# 0_8mm_Layers.net
KiCad netlist of a schematic drawn in EAGLE
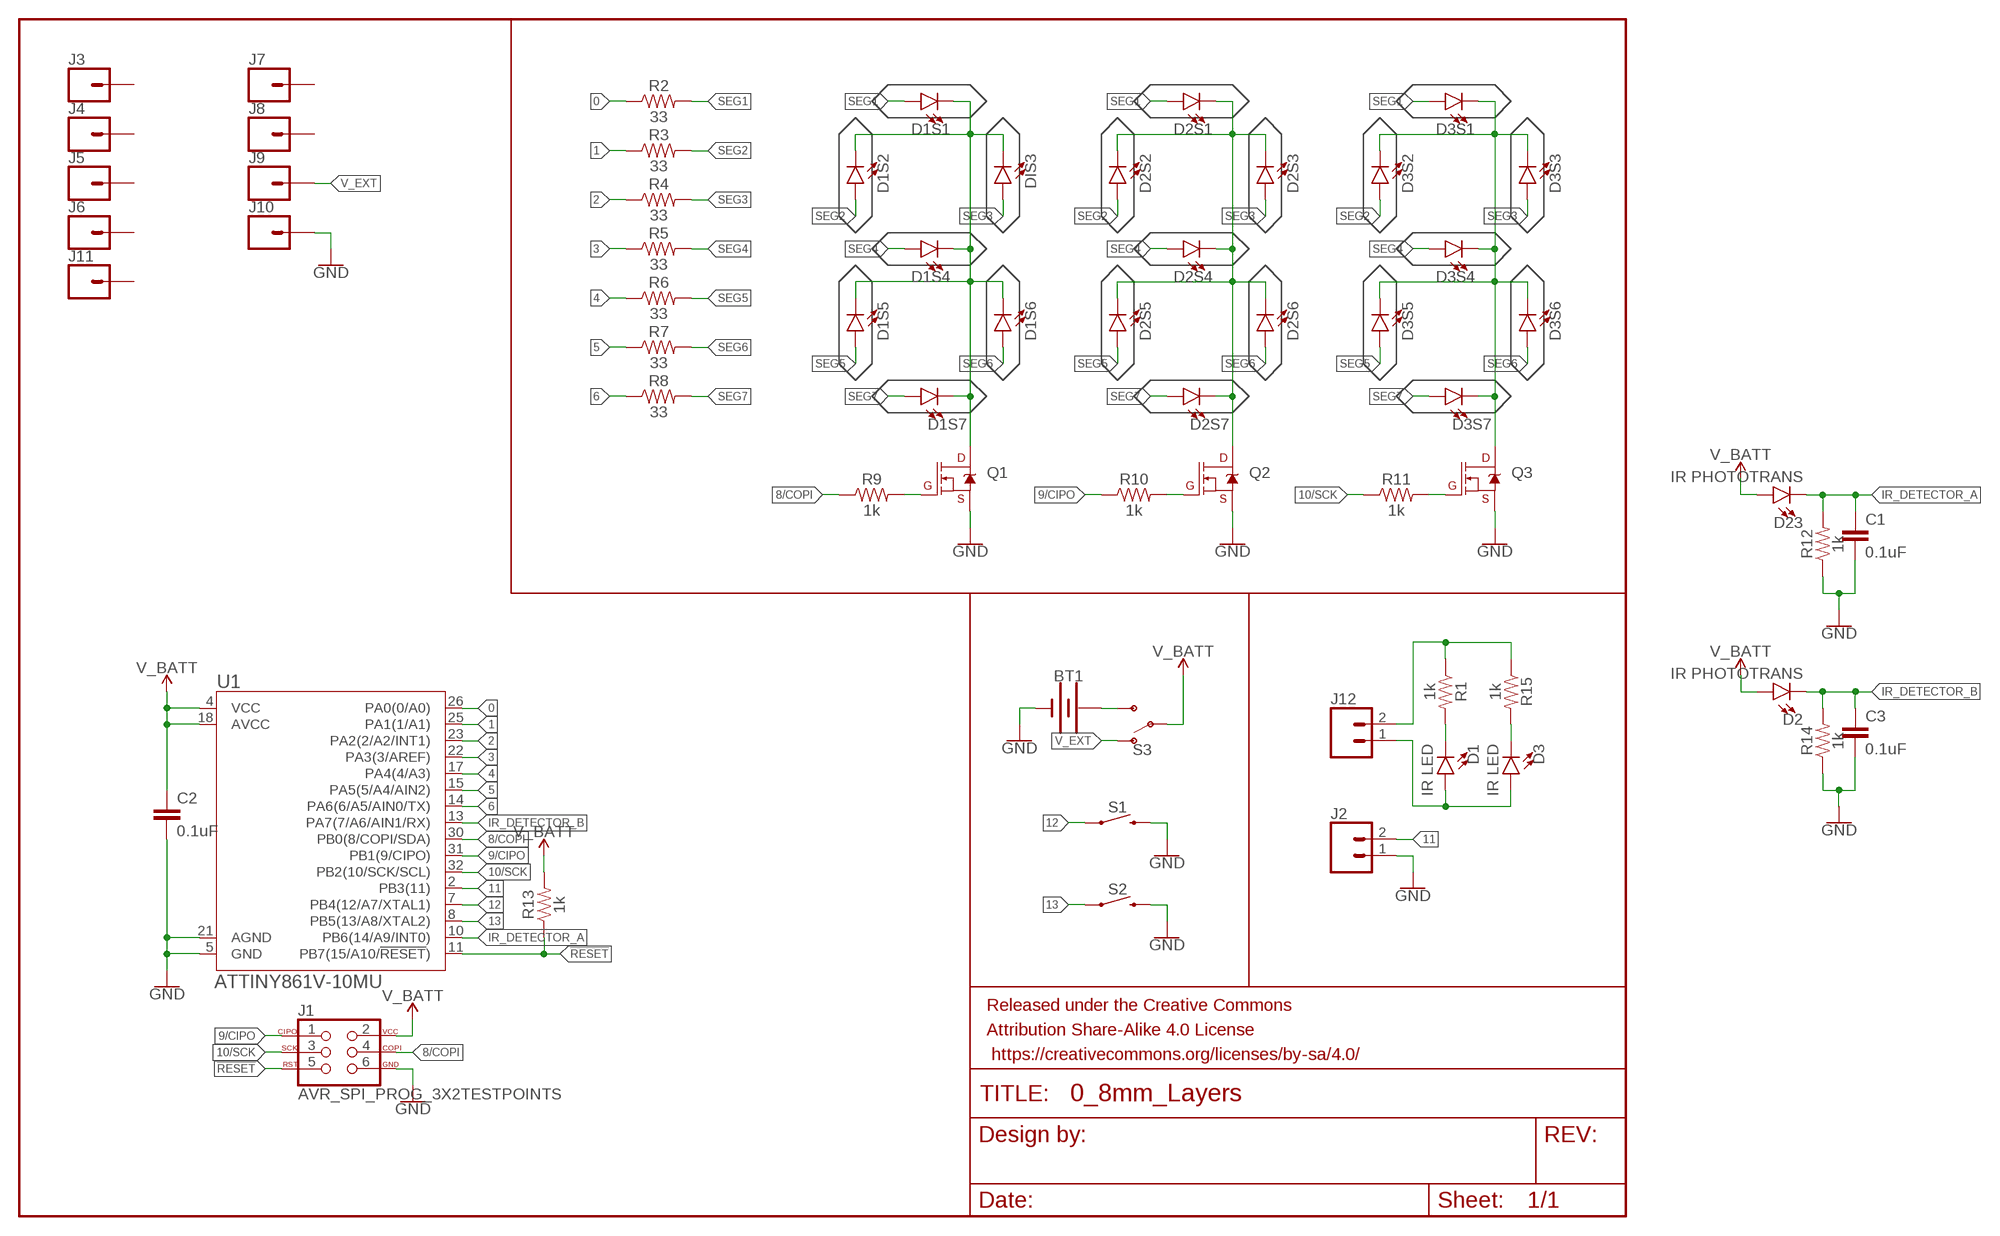
[diagram p0: schematic, sheet 1]

(export (version "E")
  (design (tool "Eeschema 10.0.6"))
  (components
    (comp (ref "BT1")
      (value "BATTERY-20MM_SMD_4LEGS_OVERPASTE_INNER")
      (footprint "eagle-import:BATTCON_20MM_4LEGS_OVERPASTE_INNER")
      (libsource (lib "eagle-import") (part "BATTERY-20MM_SMD_4LEGS_OVERPASTE_INNER"))
    )
    (comp (ref "C1")
      (value "0.1uF")
      (footprint "eagle-import:0603")
      (libsource (lib "eagle-import") (part "0.1UF-0603-25V-(+80/-20%)"))
    )
    (comp (ref "C2")
      (value "0.1uF")
      (footprint "eagle-import:0603")
      (libsource (lib "eagle-import") (part "0.1UF-0603-25V-(+80/-20%)"))
    )
    (comp (ref "C3")
      (value "0.1uF")
      (footprint "eagle-import:0603")
      (libsource (lib "eagle-import") (part "0.1UF-0603-25V-(+80/-20%)"))
    )
    (comp (ref "D1")
      (value "IR LED")
      (footprint "eagle-import:LED-0603")
      (libsource (lib "eagle-import") (part "LED-IR0603"))
    )
    (comp (ref "D1S1")
      (value "LED0603")
      (footprint "eagle-import:LED-0603")
      (libsource (lib "eagle-import") (part "LED0603"))
    )
    (comp (ref "D1S2")
      (value "LED0603")
      (footprint "eagle-import:LED-0603")
      (libsource (lib "eagle-import") (part "LED0603"))
    )
    (comp (ref "D1S4")
      (value "LED0603")
      (footprint "eagle-import:LED-0603")
      (libsource (lib "eagle-import") (part "LED0603"))
    )
    (comp (ref "D1S5")
      (value "LED0603")
      (footprint "eagle-import:LED-0603")
      (libsource (lib "eagle-import") (part "LED0603"))
    )
    (comp (ref "D1S6")
      (value "LED0603")
      (footprint "eagle-import:LED-0603")
      (libsource (lib "eagle-import") (part "LED0603"))
    )
    (comp (ref "D1S7")
      (value "LED0603")
      (footprint "eagle-import:LED-0603")
      (libsource (lib "eagle-import") (part "LED0603"))
    )
    (comp (ref "D2")
      (value "IR PHOTOTRANS")
      (footprint "eagle-import:LED-0603")
      (libsource (lib "eagle-import") (part "LED-IR0603"))
    )
    (comp (ref "D2S1")
      (value "LED0603")
      (footprint "eagle-import:LED-0603")
      (libsource (lib "eagle-import") (part "LED0603"))
    )
    (comp (ref "D2S2")
      (value "LED0603")
      (footprint "eagle-import:LED-0603")
      (libsource (lib "eagle-import") (part "LED0603"))
    )
    (comp (ref "D2S3")
      (value "LED0603")
      (footprint "eagle-import:LED-0603")
      (libsource (lib "eagle-import") (part "LED0603"))
    )
    (comp (ref "D2S4")
      (value "LED0603")
      (footprint "eagle-import:LED-0603")
      (libsource (lib "eagle-import") (part "LED0603"))
    )
    (comp (ref "D2S5")
      (value "LED0603")
      (footprint "eagle-import:LED-0603")
      (libsource (lib "eagle-import") (part "LED0603"))
    )
    (comp (ref "D2S6")
      (value "LED0603")
      (footprint "eagle-import:LED-0603")
      (libsource (lib "eagle-import") (part "LED0603"))
    )
    (comp (ref "D2S7")
      (value "LED0603")
      (footprint "eagle-import:LED-0603")
      (libsource (lib "eagle-import") (part "LED0603"))
    )
    (comp (ref "D3")
      (value "IR LED")
      (footprint "eagle-import:LED-0603")
      (libsource (lib "eagle-import") (part "LED-IR0603"))
    )
    (comp (ref "D3S1")
      (value "LED0603")
      (footprint "eagle-import:LED-0603")
      (libsource (lib "eagle-import") (part "LED0603"))
    )
    (comp (ref "D3S2")
      (value "LED0603")
      (footprint "eagle-import:LED-0603")
      (libsource (lib "eagle-import") (part "LED0603"))
    )
    (comp (ref "D3S3")
      (value "LED0603")
      (footprint "eagle-import:LED-0603")
      (libsource (lib "eagle-import") (part "LED0603"))
    )
    (comp (ref "D3S4")
      (value "LED0603")
      (footprint "eagle-import:LED-0603")
      (libsource (lib "eagle-import") (part "LED0603"))
    )
    (comp (ref "D3S5")
      (value "LED0603")
      (footprint "eagle-import:LED-0603")
      (libsource (lib "eagle-import") (part "LED0603"))
    )
    (comp (ref "D3S6")
      (value "LED0603")
      (footprint "eagle-import:LED-0603")
      (libsource (lib "eagle-import") (part "LED0603"))
    )
    (comp (ref "D3S7")
      (value "LED0603")
      (footprint "eagle-import:LED-0603")
      (libsource (lib "eagle-import") (part "LED0603"))
    )
    (comp (ref "D23")
      (value "IR PHOTOTRANS")
      (footprint "eagle-import:LED-0603")
      (libsource (lib "eagle-import") (part "LED-IR0603"))
    )
    (comp (ref "DIS3")
      (value "LED0603")
      (footprint "eagle-import:LED-0603")
      (libsource (lib "eagle-import") (part "LED0603"))
    )
    (comp (ref "FRAME1")
      (value "FRAME-LETTER")
      (footprint "eagle-import:CREATIVE_COMMONS")
      (libsource (lib "eagle-import") (part "FRAME-LETTER"))
    )
    (comp (ref "J1")
      (value "AVR_SPI_PROG_3X2TESTPOINTS")
      (footprint "eagle-import:2X3_TEST_POINTS")
      (libsource (lib "eagle-import") (part "AVR_SPI_PROG_3X2TESTPOINTS"))
    )
    (comp (ref "J2")
      (value "CONN_02")
      (footprint "eagle-import:1X02")
      (libsource (lib "eagle-import") (part "CONN_02"))
    )
    (comp (ref "J3")
      (value "CONN_01")
      (footprint "eagle-import:1X01")
      (libsource (lib "eagle-import") (part "CONN_01"))
    )
    (comp (ref "J4")
      (value "CONN_01")
      (footprint "eagle-import:1X01")
      (libsource (lib "eagle-import") (part "CONN_01"))
    )
    (comp (ref "J5")
      (value "CONN_01")
      (footprint "eagle-import:1X01")
      (libsource (lib "eagle-import") (part "CONN_01"))
    )
    (comp (ref "J6")
      (value "CONN_01")
      (footprint "eagle-import:1X01")
      (libsource (lib "eagle-import") (part "CONN_01"))
    )
    (comp (ref "J7")
      (value "CONN_01")
      (footprint "eagle-import:1X01")
      (libsource (lib "eagle-import") (part "CONN_01"))
    )
    (comp (ref "J8")
      (value "CONN_01")
      (footprint "eagle-import:1X01")
      (libsource (lib "eagle-import") (part "CONN_01"))
    )
    (comp (ref "J9")
      (value "CONN_01")
      (footprint "eagle-import:1X01")
      (libsource (lib "eagle-import") (part "CONN_01"))
    )
    (comp (ref "J10")
      (value "CONN_01")
      (footprint "eagle-import:1X01")
      (libsource (lib "eagle-import") (part "CONN_01"))
    )
    (comp (ref "J11")
      (value "CONN_01")
      (footprint "eagle-import:1X01")
      (libsource (lib "eagle-import") (part "CONN_01"))
    )
    (comp (ref "J12")
      (value "CONN_02")
      (footprint "eagle-import:1X02")
      (libsource (lib "eagle-import") (part "CONN_02"))
    )
    (comp (ref "Q1")
      (value "220mA/50V/3.5Ω")
      (footprint "eagle-import:SOT23-3")
      (libsource (lib "eagle-import") (part "MOSFET-NCH-BSS138"))
    )
    (comp (ref "Q2")
      (value "220mA/50V/3.5Ω")
      (footprint "eagle-import:SOT23-3")
      (libsource (lib "eagle-import") (part "MOSFET-NCH-BSS138"))
    )
    (comp (ref "Q3")
      (value "220mA/50V/3.5Ω")
      (footprint "eagle-import:SOT23-3")
      (libsource (lib "eagle-import") (part "MOSFET-NCH-BSS138"))
    )
    (comp (ref "R1")
      (value "1k")
      (footprint "eagle-import:0603")
      (libsource (lib "eagle-import") (part "1KOHM-0603-1/10W-1%"))
    )
    (comp (ref "R2")
      (value "33")
      (footprint "eagle-import:0603")
      (libsource (lib "eagle-import") (part "33OHM-0603-1/10W-1%"))
    )
    (comp (ref "R3")
      (value "33")
      (footprint "eagle-import:0603")
      (libsource (lib "eagle-import") (part "33OHM-0603-1/10W-1%"))
    )
    (comp (ref "R4")
      (value "33")
      (footprint "eagle-import:0603")
      (libsource (lib "eagle-import") (part "33OHM-0603-1/10W-1%"))
    )
    (comp (ref "R5")
      (value "33")
      (footprint "eagle-import:0603")
      (libsource (lib "eagle-import") (part "33OHM-0603-1/10W-1%"))
    )
    (comp (ref "R6")
      (value "33")
      (footprint "eagle-import:0603")
      (libsource (lib "eagle-import") (part "33OHM-0603-1/10W-1%"))
    )
    (comp (ref "R7")
      (value "33")
      (footprint "eagle-import:0603")
      (libsource (lib "eagle-import") (part "33OHM-0603-1/10W-1%"))
    )
    (comp (ref "R8")
      (value "33")
      (footprint "eagle-import:0603")
      (libsource (lib "eagle-import") (part "33OHM-0603-1/10W-1%"))
    )
    (comp (ref "R9")
      (value "1k")
      (footprint "eagle-import:0603")
      (libsource (lib "eagle-import") (part "1KOHM-0603-1/10W-1%"))
    )
    (comp (ref "R10")
      (value "1k")
      (footprint "eagle-import:0603")
      (libsource (lib "eagle-import") (part "1KOHM-0603-1/10W-1%"))
    )
    (comp (ref "R11")
      (value "1k")
      (footprint "eagle-import:0603")
      (libsource (lib "eagle-import") (part "1KOHM-0603-1/10W-1%"))
    )
    (comp (ref "R12")
      (value "1k")
      (footprint "eagle-import:0603")
      (libsource (lib "eagle-import") (part "1KOHM-0603-1/10W-1%"))
    )
    (comp (ref "R13")
      (value "1k")
      (footprint "eagle-import:0603")
      (libsource (lib "eagle-import") (part "1KOHM-0603-1/10W-1%"))
    )
    (comp (ref "R14")
      (value "1k")
      (footprint "eagle-import:0603")
      (libsource (lib "eagle-import") (part "1KOHM-0603-1/10W-1%"))
    )
    (comp (ref "R15")
      (value "1k")
      (footprint "eagle-import:0603")
      (libsource (lib "eagle-import") (part "1KOHM-0603-1/10W-1%"))
    )
    (comp (ref "S1")
      (value "MOMENTARY-SWITCH-SPST-SMD-5.2MM-TALL")
      (footprint "eagle-import:TACTILE_SWITCH_SMD_5.2MM")
      (libsource (lib "eagle-import") (part "MOMENTARY-SWITCH-SPST-SMD-5.2MM-TALL"))
    )
    (comp (ref "S2")
      (value "MOMENTARY-SWITCH-SPST-SMD-5.2MM-TALL")
      (footprint "eagle-import:TACTILE_SWITCH_SMD_5.2MM")
      (libsource (lib "eagle-import") (part "MOMENTARY-SWITCH-SPST-SMD-5.2MM-TALL"))
    )
    (comp (ref "S3")
      (value "SWITCH-SPDT-SMD-RIGHT-ANGLE")
      (footprint "eagle-import:SWITCH_SPST_SMD_A")
      (libsource (lib "eagle-import") (part "SWITCH-SPDT-SMD-RIGHT-ANGLE"))
    )
    (comp (ref "U1")
      (value "ATTINY861V-10MU")
      (footprint "eagle-import:32M1-A_ATM")
      (fields (field (name "COPYRIGHT") "Copyright (C) 2021 Ultra Librarian. All rights reserved."))
      (libsource (lib "eagle-import") (part "ATTINY861V-10MU"))
    )
  )
  (nets
    (net (code "1") (name "/~{RESET}") (class "Default")
      (node (ref "J1") (pin "5") (pinfunction "5_5") (pintype "passive"))
      (node (ref "R13") (pin "1") (pinfunction "1_1") (pintype "passive"))
      (node (ref "U1") (pin "11") (pinfunction "PB7(15/A10/~{RESET})_11") (pintype "bidirectional"))
    )
    (net (code "2") (name "0") (class "Default")
      (node (ref "R2") (pin "1") (pinfunction "1_1") (pintype "passive"))
      (node (ref "U1") (pin "26") (pinfunction "PA0(0/A0)_26") (pintype "bidirectional"))
    )
    (net (code "3") (name "1") (class "Default")
      (node (ref "R3") (pin "1") (pinfunction "1_1") (pintype "passive"))
      (node (ref "U1") (pin "25") (pinfunction "PA1(1/A1)_25") (pintype "bidirectional"))
    )
    (net (code "4") (name "2") (class "Default")
      (node (ref "R4") (pin "1") (pinfunction "1_1") (pintype "passive"))
      (node (ref "U1") (pin "23") (pinfunction "PA2(2/A2/INT1)_23") (pintype "bidirectional"))
    )
    (net (code "5") (name "3") (class "Default")
      (node (ref "R5") (pin "1") (pinfunction "1_1") (pintype "passive"))
      (node (ref "U1") (pin "22") (pinfunction "PA3(3/AREF)_22") (pintype "bidirectional"))
    )
    (net (code "6") (name "4") (class "Default")
      (node (ref "R6") (pin "1") (pinfunction "1_1") (pintype "passive"))
      (node (ref "U1") (pin "17") (pinfunction "PA4(4/A3)_17") (pintype "bidirectional"))
    )
    (net (code "7") (name "5") (class "Default")
      (node (ref "R7") (pin "1") (pinfunction "1_1") (pintype "passive"))
      (node (ref "U1") (pin "15") (pinfunction "PA5(5/A4/AIN2)_15") (pintype "bidirectional"))
    )
    (net (code "8") (name "6") (class "Default")
      (node (ref "R8") (pin "1") (pinfunction "1_1") (pintype "passive"))
      (node (ref "U1") (pin "14") (pinfunction "PA6(6/A5/AIN0/TX)_14") (pintype "bidirectional"))
    )
    (net (code "9") (name "8{slash}COPI") (class "Default")
      (node (ref "J1") (pin "4") (pinfunction "4_4") (pintype "passive"))
      (node (ref "R9") (pin "1") (pinfunction "1_1") (pintype "passive"))
      (node (ref "U1") (pin "30") (pinfunction "PB0(8/COPI/SDA)_30") (pintype "bidirectional"))
    )
    (net (code "10") (name "9{slash}CIPO") (class "Default")
      (node (ref "J1") (pin "1") (pinfunction "1_1") (pintype "passive"))
      (node (ref "R10") (pin "1") (pinfunction "1_1") (pintype "passive"))
      (node (ref "U1") (pin "31") (pinfunction "PB1(9/CIPO)_31") (pintype "bidirectional"))
    )
    (net (code "11") (name "10{slash}SCK") (class "Default")
      (node (ref "J1") (pin "3") (pinfunction "3_3") (pintype "passive"))
      (node (ref "R11") (pin "1") (pinfunction "1_1") (pintype "passive"))
      (node (ref "U1") (pin "32") (pinfunction "PB2(10/SCK/SCL)_32") (pintype "bidirectional"))
    )
    (net (code "12") (name "11") (class "Default")
      (node (ref "J2") (pin "2") (pinfunction "2_2") (pintype "passive"))
      (node (ref "U1") (pin "2") (pinfunction "PB3(11)_2") (pintype "bidirectional"))
    )
    (net (code "13") (name "12") (class "Default")
      (node (ref "S1") (pin "1") (pinfunction "1_1") (pintype "passive"))
      (node (ref "U1") (pin "7") (pinfunction "PB4(12/A7/XTAL1)_7") (pintype "bidirectional"))
    )
    (net (code "14") (name "13") (class "Default")
      (node (ref "S2") (pin "1") (pinfunction "1_1") (pintype "passive"))
      (node (ref "U1") (pin "8") (pinfunction "PB5(13/A8/XTAL2)_8") (pintype "bidirectional"))
    )
    (net (code "15") (name "GND") (class "Default")
      (node (ref "BT1") (pin "2") (pinfunction "-_2") (pintype "power_in"))
      (node (ref "C1") (pin "2") (pinfunction "2_2") (pintype "passive"))
      (node (ref "C2") (pin "2") (pinfunction "2_2") (pintype "passive"))
      (node (ref "C3") (pin "2") (pinfunction "2_2") (pintype "passive"))
      (node (ref "J1") (pin "6") (pinfunction "6_6") (pintype "passive"))
      (node (ref "J10") (pin "1") (pinfunction "1_1") (pintype "passive"))
      (node (ref "J2") (pin "1") (pinfunction "1_1") (pintype "passive"))
      (node (ref "Q1") (pin "2") (pinfunction "S_2") (pintype "bidirectional"))
      (node (ref "Q2") (pin "2") (pinfunction "S_2") (pintype "bidirectional"))
      (node (ref "Q3") (pin "2") (pinfunction "S_2") (pintype "bidirectional"))
      (node (ref "R12") (pin "1") (pinfunction "1_1") (pintype "passive"))
      (node (ref "R14") (pin "1") (pinfunction "1_1") (pintype "passive"))
      (node (ref "S1") (pin "3") (pinfunction "2_3") (pintype "passive"))
      (node (ref "S2") (pin "3") (pinfunction "2_3") (pintype "passive"))
      (node (ref "U1") (pin "21") (pinfunction "AGND_21") (pintype "power_in"))
      (node (ref "U1") (pin "5") (pinfunction "GND_5") (pintype "power_in"))
    )
    (net (code "16") (name "IR_DETECTOR_A") (class "Default")
      (node (ref "C1") (pin "1") (pinfunction "1_1") (pintype "passive"))
      (node (ref "D23") (pin "C") (pinfunction "C_C") (pintype "passive"))
      (node (ref "R12") (pin "2") (pinfunction "2_2") (pintype "passive"))
      (node (ref "U1") (pin "10") (pinfunction "PB6(14/A9/INT0)_10") (pintype "bidirectional"))
    )
    (net (code "17") (name "IR_DETECTOR_B") (class "Default")
      (node (ref "C3") (pin "1") (pinfunction "1_1") (pintype "passive"))
      (node (ref "D2") (pin "C") (pinfunction "C_C") (pintype "passive"))
      (node (ref "R14") (pin "2") (pinfunction "2_2") (pintype "passive"))
      (node (ref "U1") (pin "13") (pinfunction "PA7(7/A6/AIN1/RX)_13") (pintype "bidirectional"))
    )
    (net (code "18") (name "Net-(BT1-+)") (class "Default")
      (node (ref "BT1") (pin "1") (pinfunction "+_1") (pintype "power_in"))
      (node (ref "S3") (pin "3") (pinfunction "S_3") (pintype "passive"))
    )
    (net (code "19") (name "Net-(D1-PadA)") (class "Default")
      (node (ref "D1") (pin "A") (pinfunction "A_A") (pintype "passive"))
      (node (ref "D3") (pin "A") (pinfunction "A_A") (pintype "passive"))
      (node (ref "J12") (pin "1") (pinfunction "1_1") (pintype "passive"))
    )
    (net (code "20") (name "Net-(D1-PadC)") (class "Default")
      (node (ref "D1") (pin "C") (pinfunction "C_C") (pintype "passive"))
      (node (ref "R1") (pin "2") (pinfunction "2_2") (pintype "passive"))
    )
    (net (code "21") (name "Net-(D3-PadC)") (class "Default")
      (node (ref "D3") (pin "C") (pinfunction "C_C") (pintype "passive"))
      (node (ref "R15") (pin "2") (pinfunction "2_2") (pintype "passive"))
    )
    (net (code "22") (name "Net-(J12-Pad2)") (class "Default")
      (node (ref "J12") (pin "2") (pinfunction "2_2") (pintype "passive"))
      (node (ref "R1") (pin "1") (pinfunction "1_1") (pintype "passive"))
      (node (ref "R15") (pin "1") (pinfunction "1_1") (pintype "passive"))
    )
    (net (code "23") (name "Net-(Q1-D)") (class "Default")
      (node (ref "D1S1") (pin "C") (pinfunction "C_C") (pintype "passive"))
      (node (ref "D1S2") (pin "C") (pinfunction "C_C") (pintype "passive"))
      (node (ref "D1S4") (pin "C") (pinfunction "C_C") (pintype "passive"))
      (node (ref "D1S5") (pin "C") (pinfunction "C_C") (pintype "passive"))
      (node (ref "D1S6") (pin "C") (pinfunction "C_C") (pintype "passive"))
      (node (ref "D1S7") (pin "C") (pinfunction "C_C") (pintype "passive"))
      (node (ref "DIS3") (pin "C") (pinfunction "C_C") (pintype "passive"))
      (node (ref "Q1") (pin "3") (pinfunction "D_3") (pintype "bidirectional"))
    )
    (net (code "24") (name "Net-(Q1-G)") (class "Default")
      (node (ref "Q1") (pin "1") (pinfunction "G_1") (pintype "bidirectional"))
      (node (ref "R9") (pin "2") (pinfunction "2_2") (pintype "passive"))
    )
    (net (code "25") (name "Net-(Q2-D)") (class "Default")
      (node (ref "D2S1") (pin "C") (pinfunction "C_C") (pintype "passive"))
      (node (ref "D2S2") (pin "C") (pinfunction "C_C") (pintype "passive"))
      (node (ref "D2S3") (pin "C") (pinfunction "C_C") (pintype "passive"))
      (node (ref "D2S4") (pin "C") (pinfunction "C_C") (pintype "passive"))
      (node (ref "D2S5") (pin "C") (pinfunction "C_C") (pintype "passive"))
      (node (ref "D2S6") (pin "C") (pinfunction "C_C") (pintype "passive"))
      (node (ref "D2S7") (pin "C") (pinfunction "C_C") (pintype "passive"))
      (node (ref "Q2") (pin "3") (pinfunction "D_3") (pintype "bidirectional"))
    )
    (net (code "26") (name "Net-(Q2-G)") (class "Default")
      (node (ref "Q2") (pin "1") (pinfunction "G_1") (pintype "bidirectional"))
      (node (ref "R10") (pin "2") (pinfunction "2_2") (pintype "passive"))
    )
    (net (code "27") (name "Net-(Q3-D)") (class "Default")
      (node (ref "D3S1") (pin "C") (pinfunction "C_C") (pintype "passive"))
      (node (ref "D3S2") (pin "C") (pinfunction "C_C") (pintype "passive"))
      (node (ref "D3S3") (pin "C") (pinfunction "C_C") (pintype "passive"))
      (node (ref "D3S4") (pin "C") (pinfunction "C_C") (pintype "passive"))
      (node (ref "D3S5") (pin "C") (pinfunction "C_C") (pintype "passive"))
      (node (ref "D3S6") (pin "C") (pinfunction "C_C") (pintype "passive"))
      (node (ref "D3S7") (pin "C") (pinfunction "C_C") (pintype "passive"))
      (node (ref "Q3") (pin "3") (pinfunction "D_3") (pintype "bidirectional"))
    )
    (net (code "28") (name "Net-(Q3-G)") (class "Default")
      (node (ref "Q3") (pin "1") (pinfunction "G_1") (pintype "bidirectional"))
      (node (ref "R11") (pin "2") (pinfunction "2_2") (pintype "passive"))
    )
    (net (code "29") (name "SEG1") (class "Default")
      (node (ref "D1S1") (pin "A") (pinfunction "A_A") (pintype "passive"))
      (node (ref "D2S1") (pin "A") (pinfunction "A_A") (pintype "passive"))
      (node (ref "D3S1") (pin "A") (pinfunction "A_A") (pintype "passive"))
      (node (ref "R2") (pin "2") (pinfunction "2_2") (pintype "passive"))
    )
    (net (code "30") (name "SEG2") (class "Default")
      (node (ref "D1S2") (pin "A") (pinfunction "A_A") (pintype "passive"))
      (node (ref "D2S2") (pin "A") (pinfunction "A_A") (pintype "passive"))
      (node (ref "D3S2") (pin "A") (pinfunction "A_A") (pintype "passive"))
      (node (ref "R3") (pin "2") (pinfunction "2_2") (pintype "passive"))
    )
    (net (code "31") (name "SEG3") (class "Default")
      (node (ref "D2S3") (pin "A") (pinfunction "A_A") (pintype "passive"))
      (node (ref "D3S3") (pin "A") (pinfunction "A_A") (pintype "passive"))
      (node (ref "DIS3") (pin "A") (pinfunction "A_A") (pintype "passive"))
      (node (ref "R4") (pin "2") (pinfunction "2_2") (pintype "passive"))
    )
    (net (code "32") (name "SEG4") (class "Default")
      (node (ref "D1S4") (pin "A") (pinfunction "A_A") (pintype "passive"))
      (node (ref "D2S4") (pin "A") (pinfunction "A_A") (pintype "passive"))
      (node (ref "D3S4") (pin "A") (pinfunction "A_A") (pintype "passive"))
      (node (ref "R5") (pin "2") (pinfunction "2_2") (pintype "passive"))
    )
    (net (code "33") (name "SEG5") (class "Default")
      (node (ref "D1S5") (pin "A") (pinfunction "A_A") (pintype "passive"))
      (node (ref "D2S5") (pin "A") (pinfunction "A_A") (pintype "passive"))
      (node (ref "D3S5") (pin "A") (pinfunction "A_A") (pintype "passive"))
      (node (ref "R6") (pin "2") (pinfunction "2_2") (pintype "passive"))
    )
    (net (code "34") (name "SEG6") (class "Default")
      (node (ref "D1S6") (pin "A") (pinfunction "A_A") (pintype "passive"))
      (node (ref "D2S6") (pin "A") (pinfunction "A_A") (pintype "passive"))
      (node (ref "D3S6") (pin "A") (pinfunction "A_A") (pintype "passive"))
      (node (ref "R7") (pin "2") (pinfunction "2_2") (pintype "passive"))
    )
    (net (code "35") (name "SEG7") (class "Default")
      (node (ref "D1S7") (pin "A") (pinfunction "A_A") (pintype "passive"))
      (node (ref "D2S7") (pin "A") (pinfunction "A_A") (pintype "passive"))
      (node (ref "D3S7") (pin "A") (pinfunction "A_A") (pintype "passive"))
      (node (ref "R8") (pin "2") (pinfunction "2_2") (pintype "passive"))
    )
    (net (code "36") (name "V_BATT") (class "Default")
      (node (ref "C2") (pin "1") (pinfunction "1_1") (pintype "passive"))
      (node (ref "D2") (pin "A") (pinfunction "A_A") (pintype "passive"))
      (node (ref "D23") (pin "A") (pinfunction "A_A") (pintype "passive"))
      (node (ref "J1") (pin "2") (pinfunction "2_2") (pintype "passive"))
      (node (ref "R13") (pin "2") (pinfunction "2_2") (pintype "passive"))
      (node (ref "S3") (pin "2") (pinfunction "P_2") (pintype "passive"))
      (node (ref "U1") (pin "18") (pinfunction "AVCC_18") (pintype "power_in"))
      (node (ref "U1") (pin "4") (pinfunction "VCC_4") (pintype "power_in"))
    )
    (net (code "37") (name "V_EXT") (class "Default")
      (node (ref "J9") (pin "1") (pinfunction "1_1") (pintype "passive"))
      (node (ref "S3") (pin "1") (pinfunction "O_1") (pintype "passive"))
    )
    (net (code "38") (name "unconnected-(J3-Pad1)") (class "Default")
      (node (ref "J3") (pin "1") (pinfunction "1_1") (pintype "passive"))
    )
    (net (code "39") (name "unconnected-(J4-Pad1)") (class "Default")
      (node (ref "J4") (pin "1") (pinfunction "1_1") (pintype "passive"))
    )
    (net (code "40") (name "unconnected-(J5-Pad1)") (class "Default")
      (node (ref "J5") (pin "1") (pinfunction "1_1") (pintype "passive"))
    )
    (net (code "41") (name "unconnected-(J6-Pad1)") (class "Default")
      (node (ref "J6") (pin "1") (pinfunction "1_1") (pintype "passive"))
    )
    (net (code "42") (name "unconnected-(J7-Pad1)") (class "Default")
      (node (ref "J7") (pin "1") (pinfunction "1_1") (pintype "passive"))
    )
    (net (code "43") (name "unconnected-(J8-Pad1)") (class "Default")
      (node (ref "J8") (pin "1") (pinfunction "1_1") (pintype "passive"))
    )
    (net (code "44") (name "unconnected-(J11-Pad1)") (class "Default")
      (node (ref "J11") (pin "1") (pinfunction "1_1") (pintype "passive"))
    )
  )
)
